# headers.net
KiCad netlist of a schematic drawn in Altium Designer
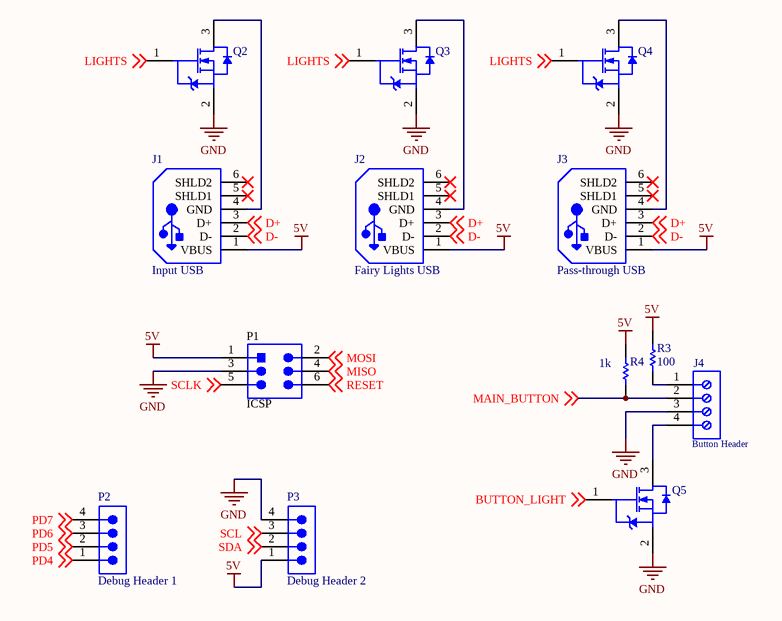
[diagram p0: headers.SchDoc]

(export (version "E")
  (design (tool "Eeschema 10.0.6"))
  (components
    (comp (ref "J1")
      (value "Input USB")
      (footprint "TE-292303-1_V")
      (fields (field (name "MANUFACTURER") "TE Connectivity") (field (name "MPN") "292303-1"))
      (libsource (lib "Altium Content Vault") (part "USB-4-2SHLD"))
    )
    (comp (ref "J2")
      (value "Fairy Lights USB")
      (footprint "TE-292303-1_V")
      (fields (field (name "MANUFACTURER") "TE Connectivity") (field (name "MPN") "292303-1"))
      (libsource (lib "Altium Content Vault") (part "USB-4-2SHLD"))
    )
    (comp (ref "J3")
      (value "Pass-through USB")
      (footprint "TE-292303-1_V")
      (fields (field (name "MANUFACTURER") "TE Connectivity") (field (name "MPN") "292303-1"))
      (libsource (lib "Altium Content Vault") (part "USB-4-2SHLD"))
    )
    (comp (ref "J4")
      (value "Button Header")
      (footprint "691508110304")
      (description "Serie 5081 - 3.50 mm Horizontal Entry SMT with Rising Cage Clamp WR-TBL, 4 pin")
      (fields
        (field (name "PART NUMBER") "691508110304")
        (field (name "MANUFACTURER") "Wurth Elektronik")
        (field (name "PUBLISHER") "WurthElektronik")
      )
      (libsource (lib "Altium Content Vault") (part "WE-CN-1P-F-TB4"))
    )
    (comp (ref "P1")
      (value "ICSP")
      (footprint "SMTC-TSW-103-08-L-D_V")
      (fields (field (name "MANUFACTURER") "Samtec") (field (name "MPN") "TSW-103-08-L-D"))
      (libsource (lib "Altium Content Vault") (part "CN-2P-M-R6"))
    )
    (comp (ref "P2")
      (value "Debug Header 1")
      (footprint "SMTC-TSW-104-08-X-S")
      (description "0.025\" SQ Post Header, Through-hole, Vertical, -55 to 105 degC, 2.54 mm Pitch, 4-Pin, Male, RoHS")
      (fields (field (name "PARTNUMBER") "TSW-104-08-T-S") (field (name "MANUFACTURER") "Samtec"))
      (libsource (lib "Altium Content Vault") (part "SMTC-TSW-104-08-X-S"))
    )
    (comp (ref "P3")
      (value "Debug Header 2")
      (footprint "SMTC-TSW-104-08-X-S")
      (description "0.025\" SQ Post Header, Through-hole, Vertical, -55 to 105 degC, 2.54 mm Pitch, 4-Pin, Male, RoHS")
      (fields (field (name "PARTNUMBER") "TSW-104-08-T-S") (field (name "MANUFACTURER") "Samtec"))
      (libsource (lib "Altium Content Vault") (part "SMTC-TSW-104-08-X-S"))
    )
    (comp (ref "Q2")
      (value "~")
      (footprint "FAIR-FDV303N-3_V")
      (fields (field (name "MANUFACTURER") "Fairchild") (field (name "MPN") "FDV303N"))
      (libsource (lib "Altium Content Vault") (part "NEMOS-GSD-3_D"))
    )
    (comp (ref "Q3")
      (value "~")
      (footprint "FAIR-FDV303N-3_V")
      (fields (field (name "MANUFACTURER") "Fairchild") (field (name "MPN") "FDV303N"))
      (libsource (lib "Altium Content Vault") (part "NEMOS-GSD-3_D"))
    )
    (comp (ref "Q4")
      (value "~")
      (footprint "FAIR-FDV303N-3_V")
      (fields (field (name "MANUFACTURER") "Fairchild") (field (name "MPN") "FDV303N"))
      (libsource (lib "Altium Content Vault") (part "NEMOS-GSD-3_D"))
    )
    (comp (ref "Q5")
      (value "~")
      (footprint "FAIR-FDV303N-3_V")
      (fields (field (name "MANUFACTURER") "Fairchild") (field (name "MPN") "FDV303N"))
      (libsource (lib "Altium Content Vault") (part "NEMOS-GSD-3_D"))
    )
    (comp (ref "R3")
      (value "100")
      (footprint "RESC2013X50X30LL20T20")
      (fields (field (name "MANUFACTURER") "Vishay Dale") (field (name "PART NUMBER") "CRCW0805100RFKEA"))
      (libsource (lib "Altium Content Vault") (part "RES"))
    )
    (comp (ref "R4")
      (value "1k")
      (footprint "RESC2013X50X30NL20T20")
      (fields (field (name "PART NUMBER") "CRCW08051K00FKEA") (field (name "MANUFACTURER") "Vishay Dale"))
      (libsource (lib "Altium Content Vault") (part "RES"))
    )
  )
  (nets
    (net (code "1") (name "5V") (class "Default")
      (node (ref "J1") (pin "1") (pinfunction "VBUS_1") (pintype "passive"))
      (node (ref "J2") (pin "1") (pinfunction "VBUS_1") (pintype "passive"))
      (node (ref "J3") (pin "1") (pinfunction "VBUS_1") (pintype "passive"))
      (node (ref "P1") (pin "1") (pinfunction "1_1") (pintype "passive"))
      (node (ref "P3") (pin "1") (pinfunction "1_1") (pintype "passive"))
      (node (ref "R3") (pin "2") (pinfunction "2_2") (pintype "passive"))
      (node (ref "R4") (pin "2") (pinfunction "2_2") (pintype "passive"))
    )
    (net (code "2") (name "BUTTON_LIGHT") (class "Default")
      (node (ref "Q5") (pin "1") (pinfunction "G_1") (pintype "passive"))
    )
    (net (code "3") (name "D+") (class "Default")
      (node (ref "J1") (pin "3") (pinfunction "D+_3") (pintype "passive"))
      (node (ref "J2") (pin "3") (pinfunction "D+_3") (pintype "passive"))
      (node (ref "J3") (pin "3") (pinfunction "D+_3") (pintype "passive"))
    )
    (net (code "4") (name "D-") (class "Default")
      (node (ref "J1") (pin "2") (pinfunction "D-_2") (pintype "passive"))
      (node (ref "J2") (pin "2") (pinfunction "D-_2") (pintype "passive"))
      (node (ref "J3") (pin "2") (pinfunction "D-_2") (pintype "passive"))
    )
    (net (code "5") (name "GND") (class "Default")
      (node (ref "J4") (pin "3") (pinfunction "3_3") (pintype "passive"))
      (node (ref "P1") (pin "3") (pinfunction "3_3") (pintype "passive"))
      (node (ref "P3") (pin "4") (pinfunction "4_4") (pintype "passive"))
      (node (ref "Q2") (pin "2") (pinfunction "S_2") (pintype "passive"))
      (node (ref "Q3") (pin "2") (pinfunction "S_2") (pintype "passive"))
      (node (ref "Q4") (pin "2") (pinfunction "S_2") (pintype "passive"))
      (node (ref "Q5") (pin "2") (pinfunction "S_2") (pintype "passive"))
    )
    (net (code "6") (name "LIGHTS") (class "Default")
      (node (ref "Q2") (pin "1") (pinfunction "G_1") (pintype "passive"))
      (node (ref "Q3") (pin "1") (pinfunction "G_1") (pintype "passive"))
      (node (ref "Q4") (pin "1") (pinfunction "G_1") (pintype "passive"))
    )
    (net (code "7") (name "MAIN_BUTTON") (class "Default")
      (node (ref "J4") (pin "2") (pinfunction "2_2") (pintype "passive"))
      (node (ref "R4") (pin "1") (pinfunction "1_1") (pintype "passive"))
    )
    (net (code "8") (name "MISO") (class "Default")
      (node (ref "P1") (pin "4") (pinfunction "4_4") (pintype "passive"))
    )
    (net (code "9") (name "MOSI") (class "Default")
      (node (ref "P1") (pin "2") (pinfunction "2_2") (pintype "passive"))
    )
    (net (code "10") (name "Net-(J1-GND)") (class "Default")
      (node (ref "J1") (pin "4") (pinfunction "GND_4") (pintype "passive"))
      (node (ref "Q2") (pin "3") (pinfunction "D_3") (pintype "passive"))
    )
    (net (code "11") (name "Net-(J2-GND)") (class "Default")
      (node (ref "J2") (pin "4") (pinfunction "GND_4") (pintype "passive"))
      (node (ref "Q3") (pin "3") (pinfunction "D_3") (pintype "passive"))
    )
    (net (code "12") (name "Net-(J3-GND)") (class "Default")
      (node (ref "J3") (pin "4") (pinfunction "GND_4") (pintype "passive"))
      (node (ref "Q4") (pin "3") (pinfunction "D_3") (pintype "passive"))
    )
    (net (code "13") (name "Net-(J4-Pad1)") (class "Default")
      (node (ref "J4") (pin "1") (pinfunction "1_1") (pintype "passive"))
      (node (ref "R3") (pin "1") (pinfunction "1_1") (pintype "passive"))
    )
    (net (code "14") (name "Net-(Q5-D)") (class "Default")
      (node (ref "J4") (pin "4") (pinfunction "4_4") (pintype "passive"))
      (node (ref "Q5") (pin "3") (pinfunction "D_3") (pintype "passive"))
    )
    (net (code "15") (name "PD4") (class "Default")
      (node (ref "P2") (pin "1") (pinfunction "1_1") (pintype "passive"))
    )
    (net (code "16") (name "PD5") (class "Default")
      (node (ref "P2") (pin "2") (pinfunction "2_2") (pintype "passive"))
    )
    (net (code "17") (name "PD6") (class "Default")
      (node (ref "P2") (pin "3") (pinfunction "3_3") (pintype "passive"))
    )
    (net (code "18") (name "PD7") (class "Default")
      (node (ref "P2") (pin "4") (pinfunction "4_4") (pintype "passive"))
    )
    (net (code "19") (name "RESET") (class "Default")
      (node (ref "P1") (pin "6") (pinfunction "6_6") (pintype "passive"))
    )
    (net (code "20") (name "SCL") (class "Default")
      (node (ref "P3") (pin "3") (pinfunction "3_3") (pintype "passive"))
    )
    (net (code "21") (name "SCLK") (class "Default")
      (node (ref "P1") (pin "5") (pinfunction "5_5") (pintype "passive"))
    )
    (net (code "22") (name "SDA") (class "Default")
      (node (ref "P3") (pin "2") (pinfunction "2_2") (pintype "passive"))
    )
    (net (code "23") (name "unconnected-(J1-SHLD1-Pad5)") (class "Default")
      (node (ref "J1") (pin "5") (pinfunction "SHLD1_5") (pintype "passive+no_connect"))
    )
    (net (code "24") (name "unconnected-(J1-SHLD2-Pad6)") (class "Default")
      (node (ref "J1") (pin "6") (pinfunction "SHLD2_6") (pintype "passive+no_connect"))
    )
    (net (code "25") (name "unconnected-(J2-SHLD1-Pad5)") (class "Default")
      (node (ref "J2") (pin "5") (pinfunction "SHLD1_5") (pintype "passive+no_connect"))
    )
    (net (code "26") (name "unconnected-(J2-SHLD2-Pad6)") (class "Default")
      (node (ref "J2") (pin "6") (pinfunction "SHLD2_6") (pintype "passive+no_connect"))
    )
    (net (code "27") (name "unconnected-(J3-SHLD1-Pad5)") (class "Default")
      (node (ref "J3") (pin "5") (pinfunction "SHLD1_5") (pintype "passive+no_connect"))
    )
    (net (code "28") (name "unconnected-(J3-SHLD2-Pad6)") (class "Default")
      (node (ref "J3") (pin "6") (pinfunction "SHLD2_6") (pintype "passive+no_connect"))
    )
  )
)
